# Apo_Board_2017_PM.net
KiCad netlist of a schematic drawn in EAGLE
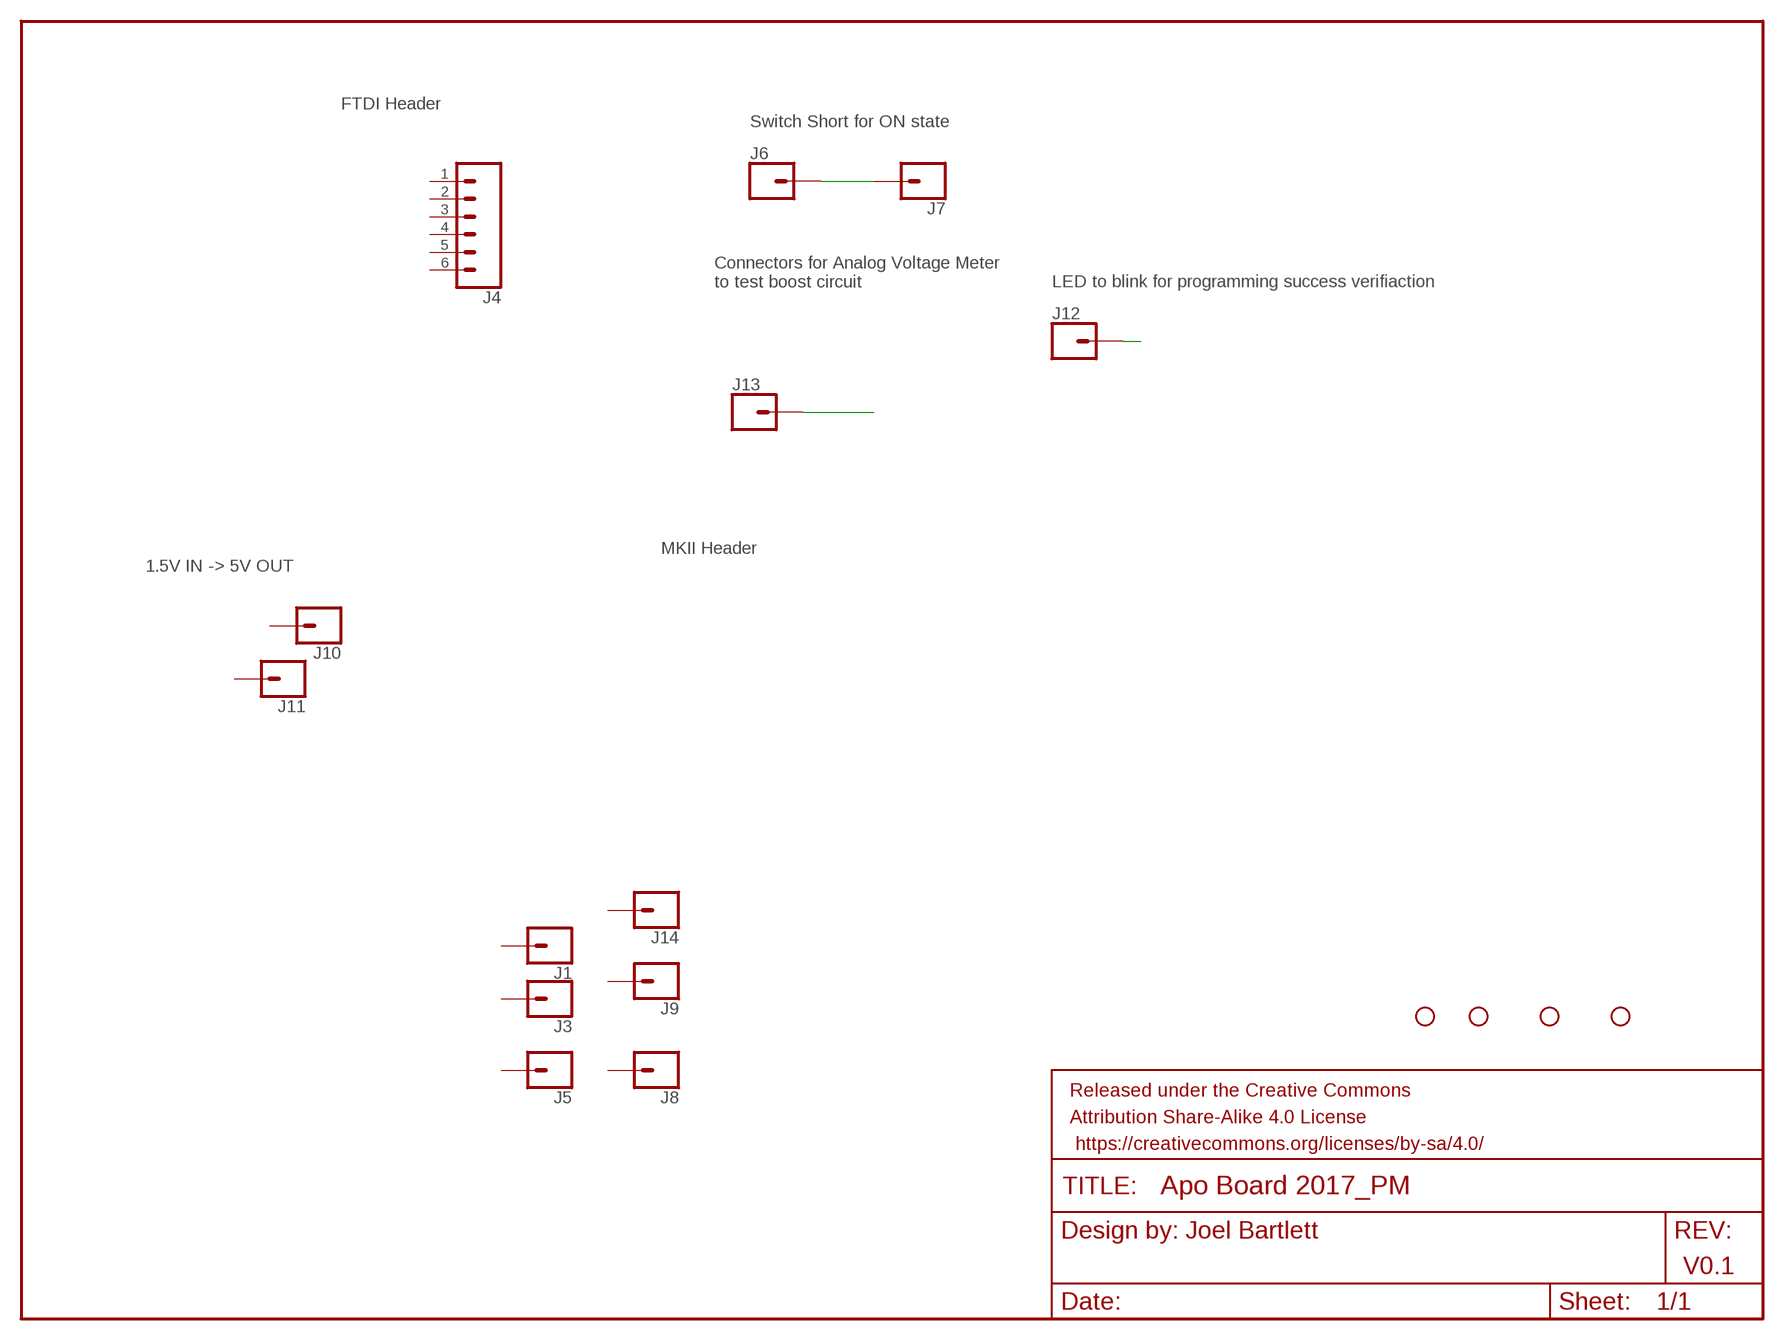
[diagram p0: schematic, sheet 1]

(export (version "E")
  (design (tool "Eeschema 10.0.6"))
  (components
    (comp (ref "FRAME1")
      (value "FRAME-LETTER")
      (footprint "eagle-import:CREATIVE_COMMONS")
      (libsource (lib "eagle-import") (part "FRAME-LETTER"))
    )
    (comp (ref "H2")
      (value "STAND-OFF")
      (footprint "eagle-import:STAND-OFF")
      (libsource (lib "eagle-import") (part "STAND-OFF"))
    )
    (comp (ref "H3")
      (value "STAND-OFF")
      (footprint "eagle-import:STAND-OFF")
      (libsource (lib "eagle-import") (part "STAND-OFF"))
    )
    (comp (ref "H4")
      (value "STAND-OFF")
      (footprint "eagle-import:STAND-OFF")
      (libsource (lib "eagle-import") (part "STAND-OFF"))
    )
    (comp (ref "H5")
      (value "STAND-OFF")
      (footprint "eagle-import:STAND-OFF")
      (libsource (lib "eagle-import") (part "STAND-OFF"))
    )
    (comp (ref "J1")
      (value "CONN_01POGOPIN_HOLE_0.58")
      (footprint "eagle-import:1X01_POGOPIN_HOLE_0.58_DIA")
      (libsource (lib "eagle-import") (part "CONN_01POGOPIN_HOLE_0.58"))
    )
    (comp (ref "J3")
      (value "CONN_01POGOPIN_HOLE_0.58")
      (footprint "eagle-import:1X01_POGOPIN_HOLE_0.58_DIA")
      (libsource (lib "eagle-import") (part "CONN_01POGOPIN_HOLE_0.58"))
    )
    (comp (ref "J4")
      (value "CONN_06POGOPIN_HOLES_ONLY")
      (footprint "eagle-import:1X06_HOLES_ONLY")
      (libsource (lib "eagle-import") (part "CONN_06POGOPIN_HOLES_ONLY"))
    )
    (comp (ref "J5")
      (value "CONN_01POGOPIN_HOLE_0.58")
      (footprint "eagle-import:1X01_POGOPIN_HOLE_0.58_DIA")
      (libsource (lib "eagle-import") (part "CONN_01POGOPIN_HOLE_0.58"))
    )
    (comp (ref "J6")
      (value "CONN_01POGOPIN_HOLE_0.58")
      (footprint "eagle-import:1X01_POGOPIN_HOLE_0.58_DIA")
      (libsource (lib "eagle-import") (part "CONN_01POGOPIN_HOLE_0.58"))
    )
    (comp (ref "J7")
      (value "CONN_01POGOPIN_HOLE_0.58")
      (footprint "eagle-import:1X01_POGOPIN_HOLE_0.58_DIA")
      (libsource (lib "eagle-import") (part "CONN_01POGOPIN_HOLE_0.58"))
    )
    (comp (ref "J8")
      (value "CONN_01POGOPIN_HOLE_0.58")
      (footprint "eagle-import:1X01_POGOPIN_HOLE_0.58_DIA")
      (libsource (lib "eagle-import") (part "CONN_01POGOPIN_HOLE_0.58"))
    )
    (comp (ref "J9")
      (value "CONN_01POGOPIN_HOLE_0.58")
      (footprint "eagle-import:1X01_POGOPIN_HOLE_0.58_DIA")
      (libsource (lib "eagle-import") (part "CONN_01POGOPIN_HOLE_0.58"))
    )
    (comp (ref "J10")
      (value "CONN_01POGOPIN_HOLE_0.58")
      (footprint "eagle-import:1X01_POGOPIN_HOLE_0.58_DIA")
      (libsource (lib "eagle-import") (part "CONN_01POGOPIN_HOLE_0.58"))
    )
    (comp (ref "J11")
      (value "CONN_01POGOPIN_HOLE_0.58")
      (footprint "eagle-import:1X01_POGOPIN_HOLE_0.58_DIA")
      (libsource (lib "eagle-import") (part "CONN_01POGOPIN_HOLE_0.58"))
    )
    (comp (ref "J12")
      (value "CONN_01POGOPIN_HOLE_0.58")
      (footprint "eagle-import:1X01_POGOPIN_HOLE_0.58_DIA")
      (libsource (lib "eagle-import") (part "CONN_01POGOPIN_HOLE_0.58"))
    )
    (comp (ref "J13")
      (value "CONN_01POGOPIN_HOLE_0.58")
      (footprint "eagle-import:1X01_POGOPIN_HOLE_0.58_DIA")
      (libsource (lib "eagle-import") (part "CONN_01POGOPIN_HOLE_0.58"))
    )
    (comp (ref "J14")
      (value "CONN_01POGOPIN_HOLE_0.58")
      (footprint "eagle-import:1X01_POGOPIN_HOLE_0.58_DIA")
      (libsource (lib "eagle-import") (part "CONN_01POGOPIN_HOLE_0.58"))
    )
  )
  (nets
    (net (code "1") (name "Net-(J6-Pad1)") (class "Default")
      (node (ref "J6") (pin "1") (pinfunction "1_1") (pintype "passive"))
      (node (ref "J7") (pin "1") (pinfunction "1_1") (pintype "passive"))
    )
    (net (code "2") (name "unconnected-(J1-Pad1)") (class "Default")
      (node (ref "J1") (pin "1") (pinfunction "1_1") (pintype "passive"))
    )
    (net (code "3") (name "unconnected-(J3-Pad1)") (class "Default")
      (node (ref "J3") (pin "1") (pinfunction "1_1") (pintype "passive"))
    )
    (net (code "4") (name "unconnected-(J4-Pad1)") (class "Default")
      (node (ref "J4") (pin "1") (pinfunction "1_1") (pintype "passive"))
    )
    (net (code "5") (name "unconnected-(J4-Pad2)") (class "Default")
      (node (ref "J4") (pin "2") (pinfunction "2_2") (pintype "passive"))
    )
    (net (code "6") (name "unconnected-(J4-Pad3)") (class "Default")
      (node (ref "J4") (pin "3") (pinfunction "3_3") (pintype "passive"))
    )
    (net (code "7") (name "unconnected-(J4-Pad4)") (class "Default")
      (node (ref "J4") (pin "4") (pinfunction "4_4") (pintype "passive"))
    )
    (net (code "8") (name "unconnected-(J4-Pad5)") (class "Default")
      (node (ref "J4") (pin "5") (pinfunction "5_5") (pintype "passive"))
    )
    (net (code "9") (name "unconnected-(J4-Pad6)") (class "Default")
      (node (ref "J4") (pin "6") (pinfunction "6_6") (pintype "passive"))
    )
    (net (code "10") (name "unconnected-(J5-Pad1)") (class "Default")
      (node (ref "J5") (pin "1") (pinfunction "1_1") (pintype "passive"))
    )
    (net (code "11") (name "unconnected-(J8-Pad1)") (class "Default")
      (node (ref "J8") (pin "1") (pinfunction "1_1") (pintype "passive"))
    )
    (net (code "12") (name "unconnected-(J9-Pad1)") (class "Default")
      (node (ref "J9") (pin "1") (pinfunction "1_1") (pintype "passive"))
    )
    (net (code "13") (name "unconnected-(J10-Pad1)") (class "Default")
      (node (ref "J10") (pin "1") (pinfunction "1_1") (pintype "passive"))
    )
    (net (code "14") (name "unconnected-(J11-Pad1)") (class "Default")
      (node (ref "J11") (pin "1") (pinfunction "1_1") (pintype "passive"))
    )
    (net (code "15") (name "unconnected-(J12-Pad1)") (class "Default")
      (node (ref "J12") (pin "1") (pinfunction "1_1") (pintype "passive"))
    )
    (net (code "16") (name "unconnected-(J13-Pad1)") (class "Default")
      (node (ref "J13") (pin "1") (pinfunction "1_1") (pintype "passive"))
    )
    (net (code "17") (name "unconnected-(J14-Pad1)") (class "Default")
      (node (ref "J14") (pin "1") (pinfunction "1_1") (pintype "passive"))
    )
  )
)
